# pixhawkDF13.net
KiCad netlist of a schematic drawn in EAGLE
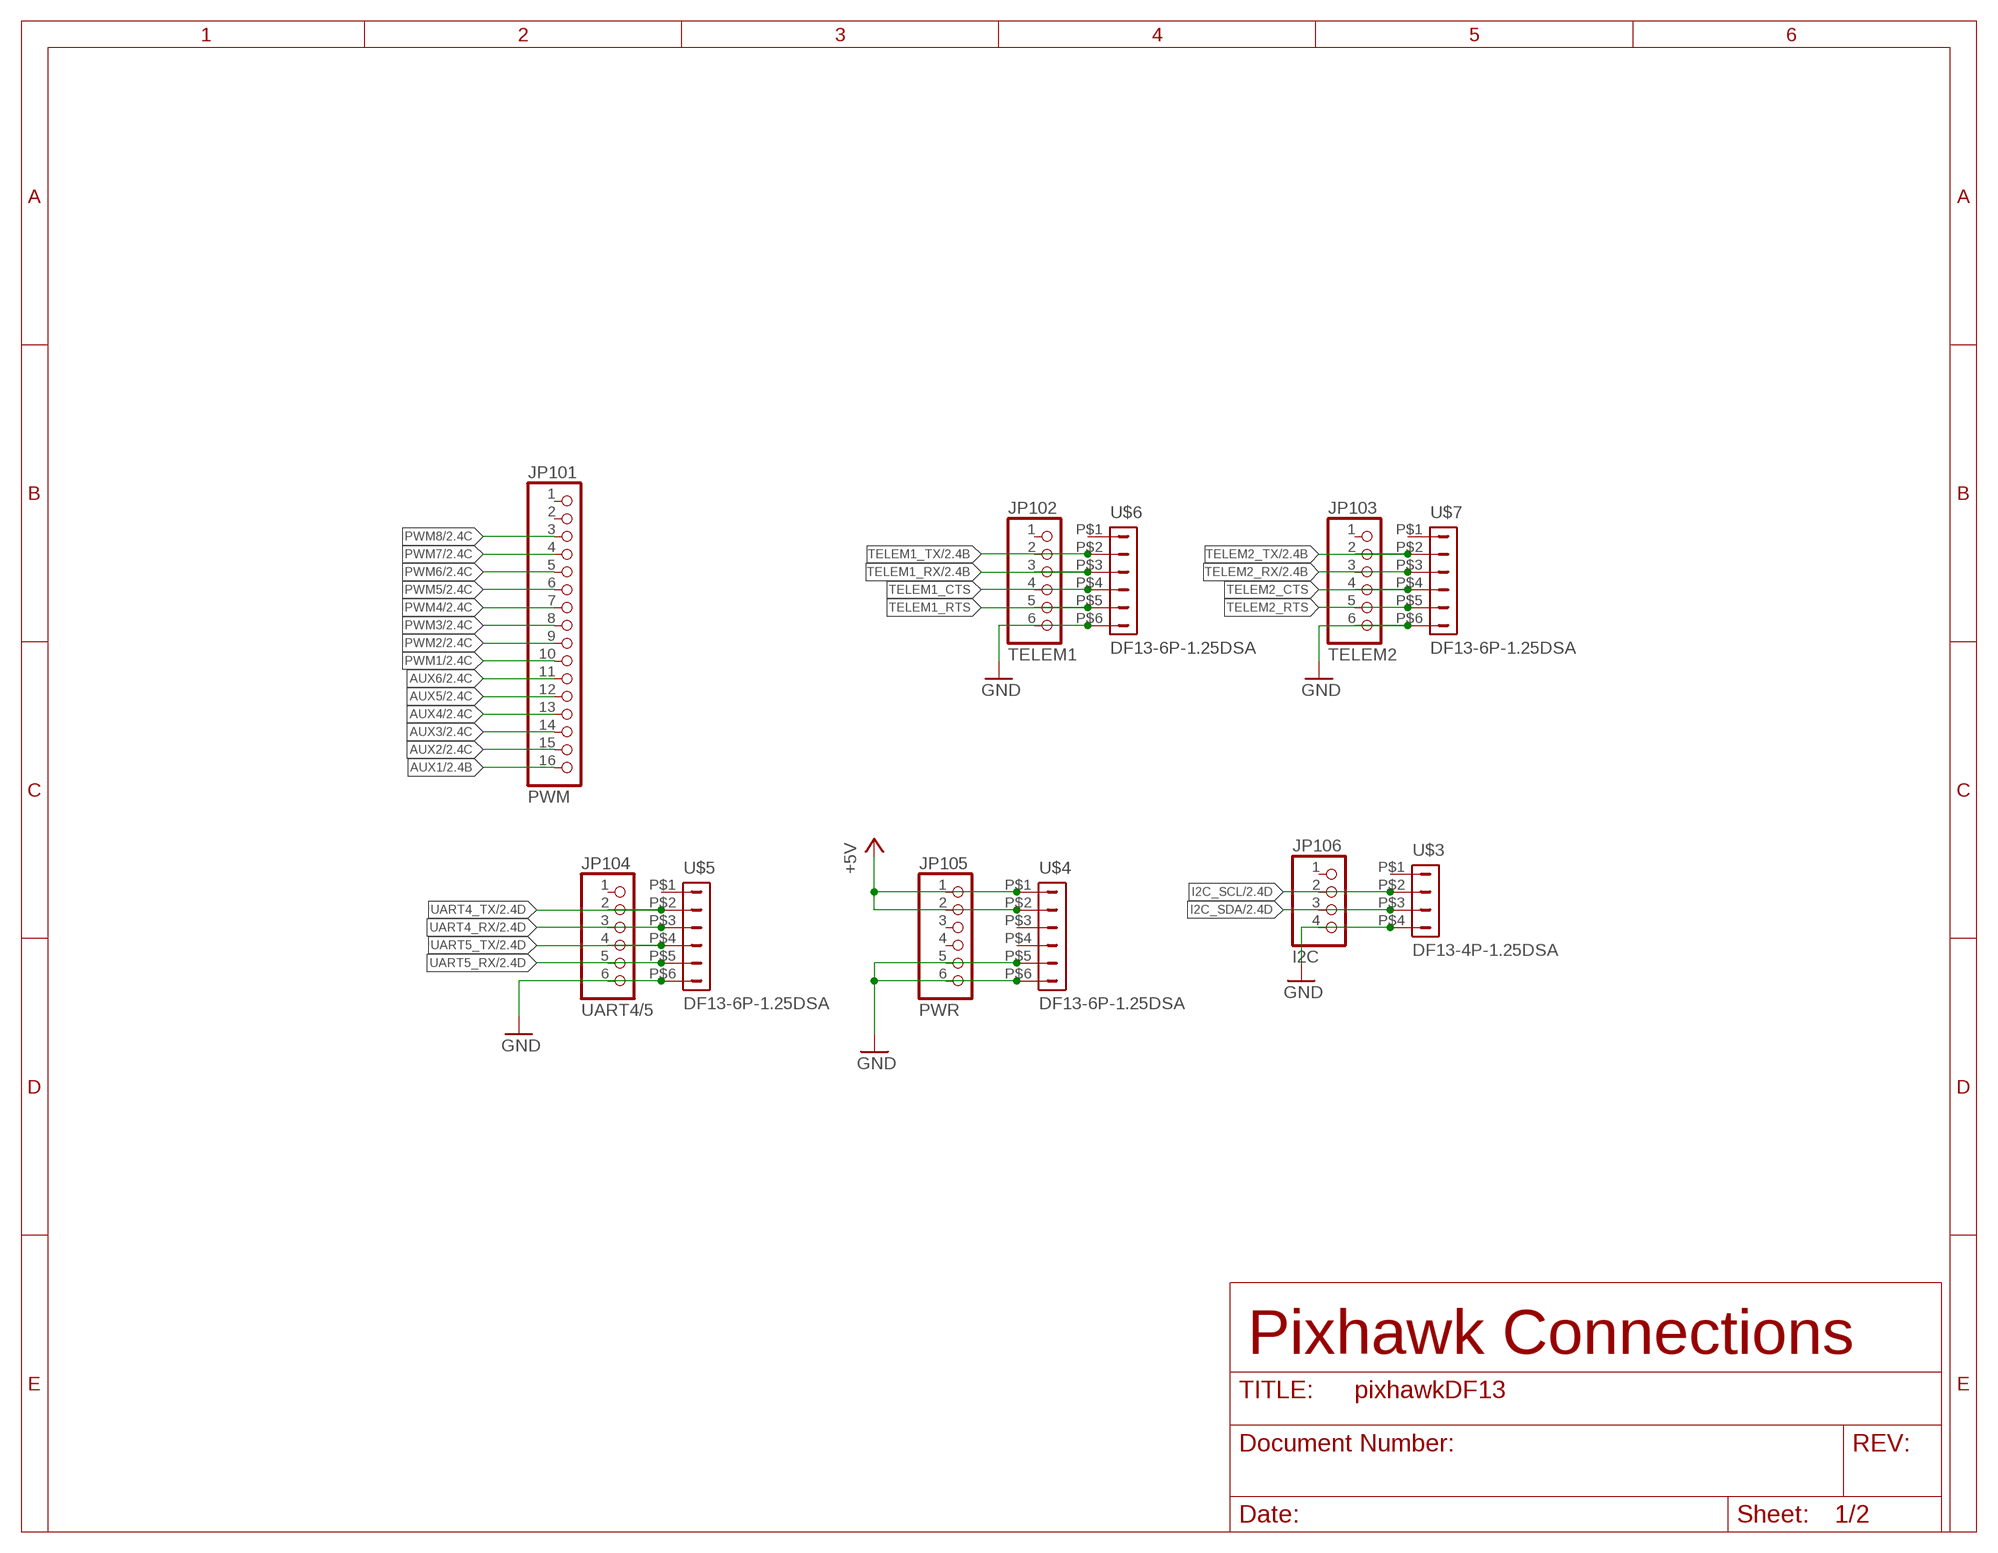
[diagram p0: schematic, sheet 1]
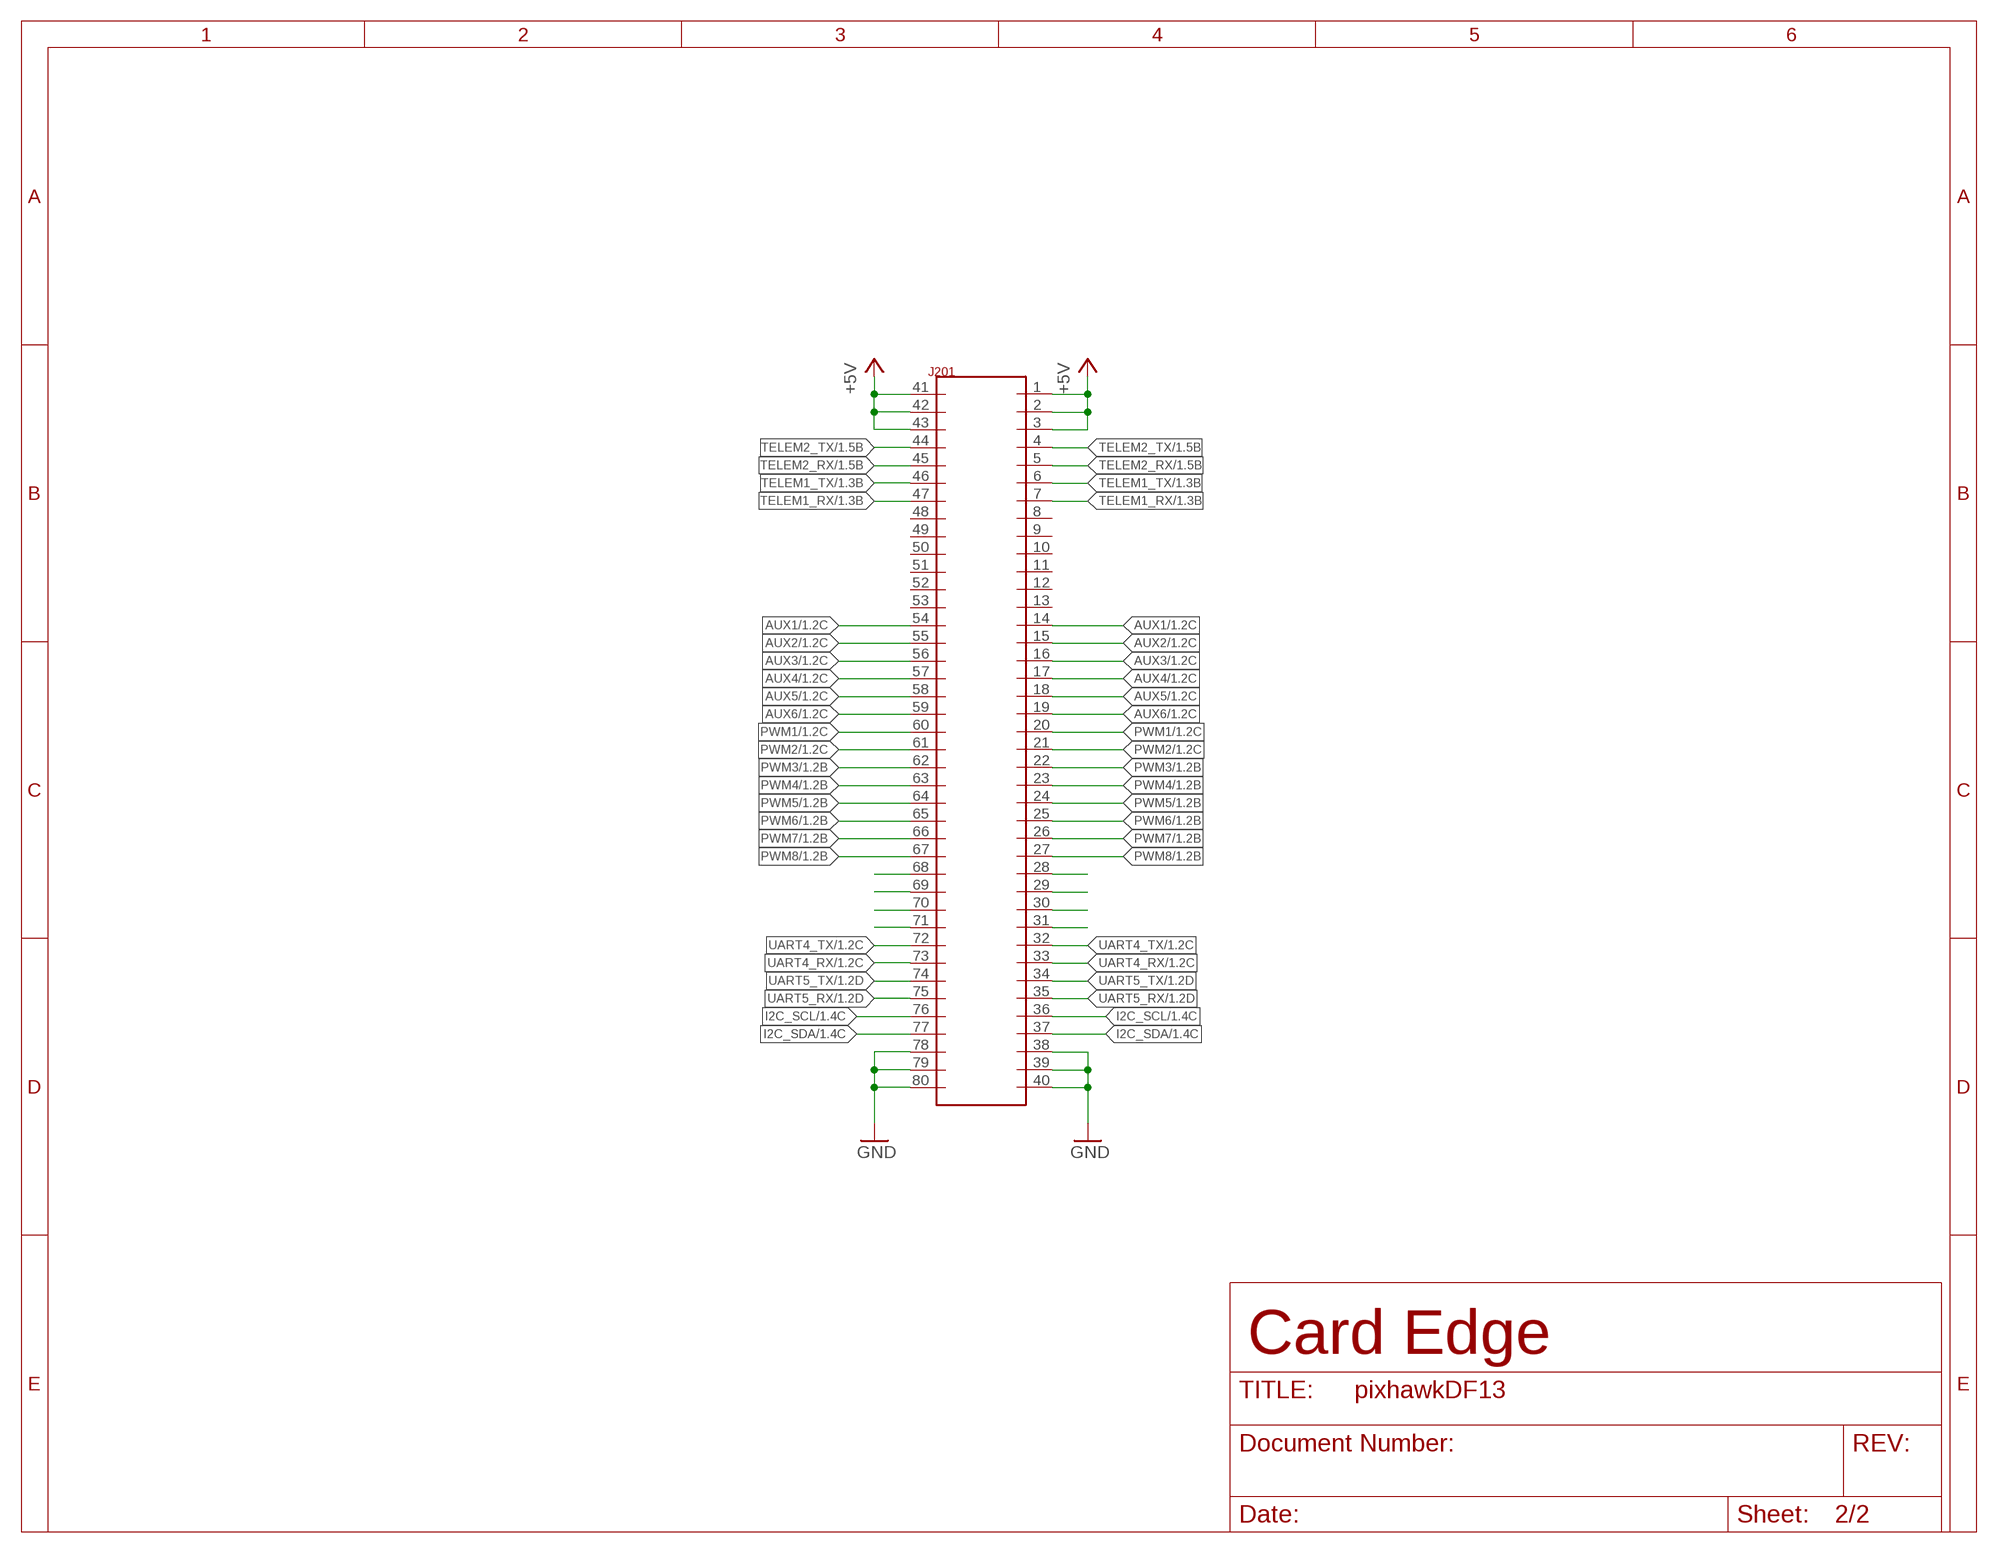
[diagram p1: schematic, sheet 2]

(export (version "E")
  (design (tool "Eeschema 10.0.6"))
  (components
    (comp (ref "J201")
      (value "80-PIN-CARD-EDGE")
      (footprint "eagle-import:80-PIN-CARD-EDGE")
      (libsource (lib "eagle-import") (part "80-PIN-CARD-EDGE"))
    )
    (comp (ref "JP101")
      (value "PWM")
      (footprint "eagle-import:1X16")
      (libsource (lib "eagle-import") (part "PINHD-1X16"))
    )
    (comp (ref "JP102")
      (value "TELEM1")
      (footprint "eagle-import:1X06")
      (libsource (lib "eagle-import") (part "PINHD-1X6"))
    )
    (comp (ref "JP103")
      (value "TELEM2")
      (footprint "eagle-import:1X06")
      (libsource (lib "eagle-import") (part "PINHD-1X6"))
    )
    (comp (ref "JP104")
      (value "UART4/5")
      (footprint "eagle-import:1X06")
      (libsource (lib "eagle-import") (part "PINHD-1X6"))
    )
    (comp (ref "JP105")
      (value "PWR")
      (footprint "eagle-import:1X06")
      (libsource (lib "eagle-import") (part "PINHD-1X6"))
    )
    (comp (ref "JP106")
      (value "I2C")
      (footprint "eagle-import:1X04")
      (libsource (lib "eagle-import") (part "PINHD-1X4"))
    )
    (comp (ref "U$3")
      (value "DF13-4P-1.25DSA")
      (footprint "eagle-import:DF13-4P-1.25DSA")
      (libsource (lib "eagle-import") (part "DF13-4P-1.25DSA"))
    )
    (comp (ref "U$4")
      (value "DF13-6P-1.25DSA")
      (footprint "eagle-import:DF13-6P-1.25DSA")
      (libsource (lib "eagle-import") (part "DF13-6P-1.25DSA"))
    )
    (comp (ref "U$5")
      (value "DF13-6P-1.25DSA")
      (footprint "eagle-import:DF13-6P-1.25DSA")
      (libsource (lib "eagle-import") (part "DF13-6P-1.25DSA"))
    )
    (comp (ref "U$6")
      (value "DF13-6P-1.25DSA")
      (footprint "eagle-import:DF13-6P-1.25DSA")
      (libsource (lib "eagle-import") (part "DF13-6P-1.25DSA"))
    )
    (comp (ref "U$7")
      (value "DF13-6P-1.25DSA")
      (footprint "eagle-import:DF13-6P-1.25DSA")
      (libsource (lib "eagle-import") (part "DF13-6P-1.25DSA"))
    )
  )
  (nets
    (net (code "1") (name "+5V") (class "Default")
      (node (ref "J201") (pin "1") (pinfunction "P$1_1") (pintype "bidirectional"))
      (node (ref "J201") (pin "2") (pinfunction "P$2_2") (pintype "bidirectional"))
      (node (ref "J201") (pin "3") (pinfunction "P$3_3") (pintype "bidirectional"))
      (node (ref "J201") (pin "41") (pinfunction "P$41_41") (pintype "bidirectional"))
      (node (ref "J201") (pin "42") (pinfunction "P$42_42") (pintype "bidirectional"))
      (node (ref "J201") (pin "43") (pinfunction "P$43_43") (pintype "bidirectional"))
      (node (ref "JP105") (pin "1") (pinfunction "1_1") (pintype "passive"))
      (node (ref "JP105") (pin "2") (pinfunction "2_2") (pintype "passive"))
      (node (ref "U$4") (pin "P$1") (pinfunction "1_P$1") (pintype "passive"))
      (node (ref "U$4") (pin "P$2") (pinfunction "2_P$2") (pintype "passive"))
    )
    (net (code "2") (name "AUX1") (class "Default")
      (node (ref "J201") (pin "14") (pinfunction "P$14_14") (pintype "bidirectional"))
      (node (ref "J201") (pin "54") (pinfunction "P$54_54") (pintype "bidirectional"))
      (node (ref "JP101") (pin "16") (pinfunction "16_16") (pintype "passive"))
    )
    (net (code "3") (name "AUX2") (class "Default")
      (node (ref "J201") (pin "15") (pinfunction "P$15_15") (pintype "bidirectional"))
      (node (ref "J201") (pin "55") (pinfunction "P$55_55") (pintype "bidirectional"))
      (node (ref "JP101") (pin "15") (pinfunction "15_15") (pintype "passive"))
    )
    (net (code "4") (name "AUX3") (class "Default")
      (node (ref "J201") (pin "16") (pinfunction "P$16_16") (pintype "bidirectional"))
      (node (ref "J201") (pin "56") (pinfunction "P$56_56") (pintype "bidirectional"))
      (node (ref "JP101") (pin "14") (pinfunction "14_14") (pintype "passive"))
    )
    (net (code "5") (name "AUX4") (class "Default")
      (node (ref "J201") (pin "17") (pinfunction "P$17_17") (pintype "bidirectional"))
      (node (ref "J201") (pin "57") (pinfunction "P$57_57") (pintype "bidirectional"))
      (node (ref "JP101") (pin "13") (pinfunction "13_13") (pintype "passive"))
    )
    (net (code "6") (name "AUX5") (class "Default")
      (node (ref "J201") (pin "18") (pinfunction "P$18_18") (pintype "bidirectional"))
      (node (ref "J201") (pin "58") (pinfunction "P$58_58") (pintype "bidirectional"))
      (node (ref "JP101") (pin "12") (pinfunction "12_12") (pintype "passive"))
    )
    (net (code "7") (name "AUX6") (class "Default")
      (node (ref "J201") (pin "19") (pinfunction "P$19_19") (pintype "bidirectional"))
      (node (ref "J201") (pin "59") (pinfunction "P$59_59") (pintype "bidirectional"))
      (node (ref "JP101") (pin "11") (pinfunction "11_11") (pintype "passive"))
    )
    (net (code "8") (name "CAN_H") (class "Default")
      (node (ref "J201") (pin "30") (pinfunction "P$30_30") (pintype "bidirectional"))
      (node (ref "J201") (pin "70") (pinfunction "P$70_70") (pintype "bidirectional"))
    )
    (net (code "9") (name "CAN_L") (class "Default")
      (node (ref "J201") (pin "31") (pinfunction "P$31_31") (pintype "bidirectional"))
      (node (ref "J201") (pin "71") (pinfunction "P$71_71") (pintype "bidirectional"))
    )
    (net (code "10") (name "GND") (class "Default")
      (node (ref "J201") (pin "38") (pinfunction "P$38_38") (pintype "bidirectional"))
      (node (ref "J201") (pin "39") (pinfunction "P$39_39") (pintype "bidirectional"))
      (node (ref "J201") (pin "40") (pinfunction "P$40_40") (pintype "bidirectional"))
      (node (ref "J201") (pin "78") (pinfunction "P$78_78") (pintype "bidirectional"))
      (node (ref "J201") (pin "79") (pinfunction "P$79_79") (pintype "bidirectional"))
      (node (ref "J201") (pin "80") (pinfunction "P$80_80") (pintype "bidirectional"))
      (node (ref "JP102") (pin "6") (pinfunction "6_6") (pintype "passive"))
      (node (ref "JP103") (pin "6") (pinfunction "6_6") (pintype "passive"))
      (node (ref "JP104") (pin "6") (pinfunction "6_6") (pintype "passive"))
      (node (ref "JP105") (pin "5") (pinfunction "5_5") (pintype "passive"))
      (node (ref "JP105") (pin "6") (pinfunction "6_6") (pintype "passive"))
      (node (ref "JP106") (pin "4") (pinfunction "4_4") (pintype "passive"))
      (node (ref "U$3") (pin "P$4") (pinfunction "4_P$4") (pintype "passive"))
      (node (ref "U$4") (pin "P$5") (pinfunction "5_P$5") (pintype "passive"))
      (node (ref "U$4") (pin "P$6") (pinfunction "6_P$6") (pintype "passive"))
      (node (ref "U$5") (pin "P$6") (pinfunction "6_P$6") (pintype "passive"))
      (node (ref "U$6") (pin "P$6") (pinfunction "6_P$6") (pintype "passive"))
      (node (ref "U$7") (pin "P$6") (pinfunction "6_P$6") (pintype "passive"))
    )
    (net (code "11") (name "I2C_SCL") (class "Default")
      (node (ref "J201") (pin "36") (pinfunction "P$36_36") (pintype "bidirectional"))
      (node (ref "J201") (pin "76") (pinfunction "P$76_76") (pintype "bidirectional"))
      (node (ref "JP106") (pin "2") (pinfunction "2_2") (pintype "passive"))
      (node (ref "U$3") (pin "P$2") (pinfunction "2_P$2") (pintype "passive"))
    )
    (net (code "12") (name "I2C_SDA") (class "Default")
      (node (ref "J201") (pin "37") (pinfunction "P$37_37") (pintype "bidirectional"))
      (node (ref "J201") (pin "77") (pinfunction "P$77_77") (pintype "bidirectional"))
      (node (ref "JP106") (pin "3") (pinfunction "3_3") (pintype "passive"))
      (node (ref "U$3") (pin "P$3") (pinfunction "3_P$3") (pintype "passive"))
    )
    (net (code "13") (name "PWM1") (class "Default")
      (node (ref "J201") (pin "20") (pinfunction "P$20_20") (pintype "bidirectional"))
      (node (ref "J201") (pin "60") (pinfunction "P$60_60") (pintype "bidirectional"))
      (node (ref "JP101") (pin "10") (pinfunction "10_10") (pintype "passive"))
    )
    (net (code "14") (name "PWM2") (class "Default")
      (node (ref "J201") (pin "21") (pinfunction "P$21_21") (pintype "bidirectional"))
      (node (ref "J201") (pin "61") (pinfunction "P$61_61") (pintype "bidirectional"))
      (node (ref "JP101") (pin "9") (pinfunction "9_9") (pintype "passive"))
    )
    (net (code "15") (name "PWM3") (class "Default")
      (node (ref "J201") (pin "22") (pinfunction "P$22_22") (pintype "bidirectional"))
      (node (ref "J201") (pin "62") (pinfunction "P$62_62") (pintype "bidirectional"))
      (node (ref "JP101") (pin "8") (pinfunction "8_8") (pintype "passive"))
    )
    (net (code "16") (name "PWM4") (class "Default")
      (node (ref "J201") (pin "23") (pinfunction "P$23_23") (pintype "bidirectional"))
      (node (ref "J201") (pin "63") (pinfunction "P$63_63") (pintype "bidirectional"))
      (node (ref "JP101") (pin "7") (pinfunction "7_7") (pintype "passive"))
    )
    (net (code "17") (name "PWM5") (class "Default")
      (node (ref "J201") (pin "24") (pinfunction "P$24_24") (pintype "bidirectional"))
      (node (ref "J201") (pin "64") (pinfunction "P$64_64") (pintype "bidirectional"))
      (node (ref "JP101") (pin "6") (pinfunction "6_6") (pintype "passive"))
    )
    (net (code "18") (name "PWM6") (class "Default")
      (node (ref "J201") (pin "25") (pinfunction "P$25_25") (pintype "bidirectional"))
      (node (ref "J201") (pin "65") (pinfunction "P$65_65") (pintype "bidirectional"))
      (node (ref "JP101") (pin "5") (pinfunction "5_5") (pintype "passive"))
    )
    (net (code "19") (name "PWM7") (class "Default")
      (node (ref "J201") (pin "26") (pinfunction "P$26_26") (pintype "bidirectional"))
      (node (ref "J201") (pin "66") (pinfunction "P$66_66") (pintype "bidirectional"))
      (node (ref "JP101") (pin "4") (pinfunction "4_4") (pintype "passive"))
    )
    (net (code "20") (name "PWM8") (class "Default")
      (node (ref "J201") (pin "27") (pinfunction "P$27_27") (pintype "bidirectional"))
      (node (ref "J201") (pin "67") (pinfunction "P$67_67") (pintype "bidirectional"))
      (node (ref "JP101") (pin "3") (pinfunction "3_3") (pintype "passive"))
    )
    (net (code "21") (name "TELEM1_CTS") (class "Default")
      (node (ref "JP102") (pin "4") (pinfunction "4_4") (pintype "passive"))
      (node (ref "U$6") (pin "P$4") (pinfunction "4_P$4") (pintype "passive"))
    )
    (net (code "22") (name "TELEM1_RTS") (class "Default")
      (node (ref "JP102") (pin "5") (pinfunction "5_5") (pintype "passive"))
      (node (ref "U$6") (pin "P$5") (pinfunction "5_P$5") (pintype "passive"))
    )
    (net (code "23") (name "TELEM1_RX") (class "Default")
      (node (ref "J201") (pin "47") (pinfunction "P$47_47") (pintype "bidirectional"))
      (node (ref "J201") (pin "7") (pinfunction "P$7_7") (pintype "bidirectional"))
      (node (ref "JP102") (pin "3") (pinfunction "3_3") (pintype "passive"))
      (node (ref "U$6") (pin "P$3") (pinfunction "3_P$3") (pintype "passive"))
    )
    (net (code "24") (name "TELEM1_TX") (class "Default")
      (node (ref "J201") (pin "46") (pinfunction "P$46_46") (pintype "bidirectional"))
      (node (ref "J201") (pin "6") (pinfunction "P$6_6") (pintype "bidirectional"))
      (node (ref "JP102") (pin "2") (pinfunction "2_2") (pintype "passive"))
      (node (ref "U$6") (pin "P$2") (pinfunction "2_P$2") (pintype "passive"))
    )
    (net (code "25") (name "TELEM2_CTS") (class "Default")
      (node (ref "JP103") (pin "4") (pinfunction "4_4") (pintype "passive"))
      (node (ref "U$7") (pin "P$4") (pinfunction "4_P$4") (pintype "passive"))
    )
    (net (code "26") (name "TELEM2_RTS") (class "Default")
      (node (ref "JP103") (pin "5") (pinfunction "5_5") (pintype "passive"))
      (node (ref "U$7") (pin "P$5") (pinfunction "5_P$5") (pintype "passive"))
    )
    (net (code "27") (name "TELEM2_RX") (class "Default")
      (node (ref "J201") (pin "45") (pinfunction "P$45_45") (pintype "bidirectional"))
      (node (ref "J201") (pin "5") (pinfunction "P$5_5") (pintype "bidirectional"))
      (node (ref "JP103") (pin "3") (pinfunction "3_3") (pintype "passive"))
      (node (ref "U$7") (pin "P$3") (pinfunction "3_P$3") (pintype "passive"))
    )
    (net (code "28") (name "TELEM2_TX") (class "Default")
      (node (ref "J201") (pin "4") (pinfunction "P$4_4") (pintype "bidirectional"))
      (node (ref "J201") (pin "44") (pinfunction "P$44_44") (pintype "bidirectional"))
      (node (ref "JP103") (pin "2") (pinfunction "2_2") (pintype "passive"))
      (node (ref "U$7") (pin "P$2") (pinfunction "2_P$2") (pintype "passive"))
    )
    (net (code "29") (name "UART4_RX") (class "Default")
      (node (ref "J201") (pin "33") (pinfunction "P$33_33") (pintype "bidirectional"))
      (node (ref "J201") (pin "73") (pinfunction "P$73_73") (pintype "bidirectional"))
      (node (ref "JP104") (pin "3") (pinfunction "3_3") (pintype "passive"))
      (node (ref "U$5") (pin "P$3") (pinfunction "3_P$3") (pintype "passive"))
    )
    (net (code "30") (name "UART4_TX") (class "Default")
      (node (ref "J201") (pin "32") (pinfunction "P$32_32") (pintype "bidirectional"))
      (node (ref "J201") (pin "72") (pinfunction "P$72_72") (pintype "bidirectional"))
      (node (ref "JP104") (pin "2") (pinfunction "2_2") (pintype "passive"))
      (node (ref "U$5") (pin "P$2") (pinfunction "2_P$2") (pintype "passive"))
    )
    (net (code "31") (name "UART5_RX") (class "Default")
      (node (ref "J201") (pin "35") (pinfunction "P$35_35") (pintype "bidirectional"))
      (node (ref "J201") (pin "75") (pinfunction "P$75_75") (pintype "bidirectional"))
      (node (ref "JP104") (pin "5") (pinfunction "5_5") (pintype "passive"))
      (node (ref "U$5") (pin "P$5") (pinfunction "5_P$5") (pintype "passive"))
    )
    (net (code "32") (name "UART5_TX") (class "Default")
      (node (ref "J201") (pin "34") (pinfunction "P$34_34") (pintype "bidirectional"))
      (node (ref "J201") (pin "74") (pinfunction "P$74_74") (pintype "bidirectional"))
      (node (ref "JP104") (pin "4") (pinfunction "4_4") (pintype "passive"))
      (node (ref "U$5") (pin "P$4") (pinfunction "4_P$4") (pintype "passive"))
    )
    (net (code "33") (name "unconnected-(J201-P$8-Pad8)") (class "Default")
      (node (ref "J201") (pin "8") (pinfunction "P$8_8") (pintype "bidirectional"))
    )
    (net (code "34") (name "unconnected-(J201-P$9-Pad9)") (class "Default")
      (node (ref "J201") (pin "9") (pinfunction "P$9_9") (pintype "bidirectional"))
    )
    (net (code "35") (name "unconnected-(J201-P$10-Pad10)") (class "Default")
      (node (ref "J201") (pin "10") (pinfunction "P$10_10") (pintype "bidirectional"))
    )
    (net (code "36") (name "unconnected-(J201-P$11-Pad11)") (class "Default")
      (node (ref "J201") (pin "11") (pinfunction "P$11_11") (pintype "bidirectional"))
    )
    (net (code "37") (name "unconnected-(J201-P$12-Pad12)") (class "Default")
      (node (ref "J201") (pin "12") (pinfunction "P$12_12") (pintype "bidirectional"))
    )
    (net (code "38") (name "unconnected-(J201-P$13-Pad13)") (class "Default")
      (node (ref "J201") (pin "13") (pinfunction "P$13_13") (pintype "bidirectional"))
    )
    (net (code "39") (name "unconnected-(J201-P$28-Pad28)") (class "Default")
      (node (ref "J201") (pin "28") (pinfunction "P$28_28") (pintype "bidirectional"))
    )
    (net (code "40") (name "unconnected-(J201-P$29-Pad29)") (class "Default")
      (node (ref "J201") (pin "29") (pinfunction "P$29_29") (pintype "bidirectional"))
    )
    (net (code "41") (name "unconnected-(J201-P$48-Pad48)") (class "Default")
      (node (ref "J201") (pin "48") (pinfunction "P$48_48") (pintype "bidirectional"))
    )
    (net (code "42") (name "unconnected-(J201-P$49-Pad49)") (class "Default")
      (node (ref "J201") (pin "49") (pinfunction "P$49_49") (pintype "bidirectional"))
    )
    (net (code "43") (name "unconnected-(J201-P$50-Pad50)") (class "Default")
      (node (ref "J201") (pin "50") (pinfunction "P$50_50") (pintype "bidirectional"))
    )
    (net (code "44") (name "unconnected-(J201-P$51-Pad51)") (class "Default")
      (node (ref "J201") (pin "51") (pinfunction "P$51_51") (pintype "bidirectional"))
    )
    (net (code "45") (name "unconnected-(J201-P$52-Pad52)") (class "Default")
      (node (ref "J201") (pin "52") (pinfunction "P$52_52") (pintype "bidirectional"))
    )
    (net (code "46") (name "unconnected-(J201-P$53-Pad53)") (class "Default")
      (node (ref "J201") (pin "53") (pinfunction "P$53_53") (pintype "bidirectional"))
    )
    (net (code "47") (name "unconnected-(J201-P$68-Pad68)") (class "Default")
      (node (ref "J201") (pin "68") (pinfunction "P$68_68") (pintype "bidirectional"))
    )
    (net (code "48") (name "unconnected-(J201-P$69-Pad69)") (class "Default")
      (node (ref "J201") (pin "69") (pinfunction "P$69_69") (pintype "bidirectional"))
    )
    (net (code "49") (name "unconnected-(JP101-Pad1)") (class "Default")
      (node (ref "JP101") (pin "1") (pinfunction "1_1") (pintype "passive"))
    )
    (net (code "50") (name "unconnected-(JP101-Pad2)") (class "Default")
      (node (ref "JP101") (pin "2") (pinfunction "2_2") (pintype "passive"))
    )
    (net (code "51") (name "unconnected-(JP102-Pad1)") (class "Default")
      (node (ref "JP102") (pin "1") (pinfunction "1_1") (pintype "passive"))
    )
    (net (code "52") (name "unconnected-(JP103-Pad1)") (class "Default")
      (node (ref "JP103") (pin "1") (pinfunction "1_1") (pintype "passive"))
    )
    (net (code "53") (name "unconnected-(JP104-Pad1)") (class "Default")
      (node (ref "JP104") (pin "1") (pinfunction "1_1") (pintype "passive"))
    )
    (net (code "54") (name "unconnected-(JP105-Pad3)") (class "Default")
      (node (ref "JP105") (pin "3") (pinfunction "3_3") (pintype "passive"))
    )
    (net (code "55") (name "unconnected-(JP105-Pad4)") (class "Default")
      (node (ref "JP105") (pin "4") (pinfunction "4_4") (pintype "passive"))
    )
    (net (code "56") (name "unconnected-(JP106-Pad1)") (class "Default")
      (node (ref "JP106") (pin "1") (pinfunction "1_1") (pintype "passive"))
    )
    (net (code "57") (name "unconnected-(U$3-1-PadP$1)") (class "Default")
      (node (ref "U$3") (pin "P$1") (pinfunction "1_P$1") (pintype "passive"))
    )
    (net (code "58") (name "unconnected-(U$4-3-PadP$3)") (class "Default")
      (node (ref "U$4") (pin "P$3") (pinfunction "3_P$3") (pintype "passive"))
    )
    (net (code "59") (name "unconnected-(U$4-4-PadP$4)") (class "Default")
      (node (ref "U$4") (pin "P$4") (pinfunction "4_P$4") (pintype "passive"))
    )
    (net (code "60") (name "unconnected-(U$5-1-PadP$1)") (class "Default")
      (node (ref "U$5") (pin "P$1") (pinfunction "1_P$1") (pintype "passive"))
    )
    (net (code "61") (name "unconnected-(U$6-1-PadP$1)") (class "Default")
      (node (ref "U$6") (pin "P$1") (pinfunction "1_P$1") (pintype "passive"))
    )
    (net (code "62") (name "unconnected-(U$7-1-PadP$1)") (class "Default")
      (node (ref "U$7") (pin "P$1") (pinfunction "1_P$1") (pintype "passive"))
    )
  )
)
